# 9volt_rail.net
KiCad netlist of a schematic drawn in EAGLE
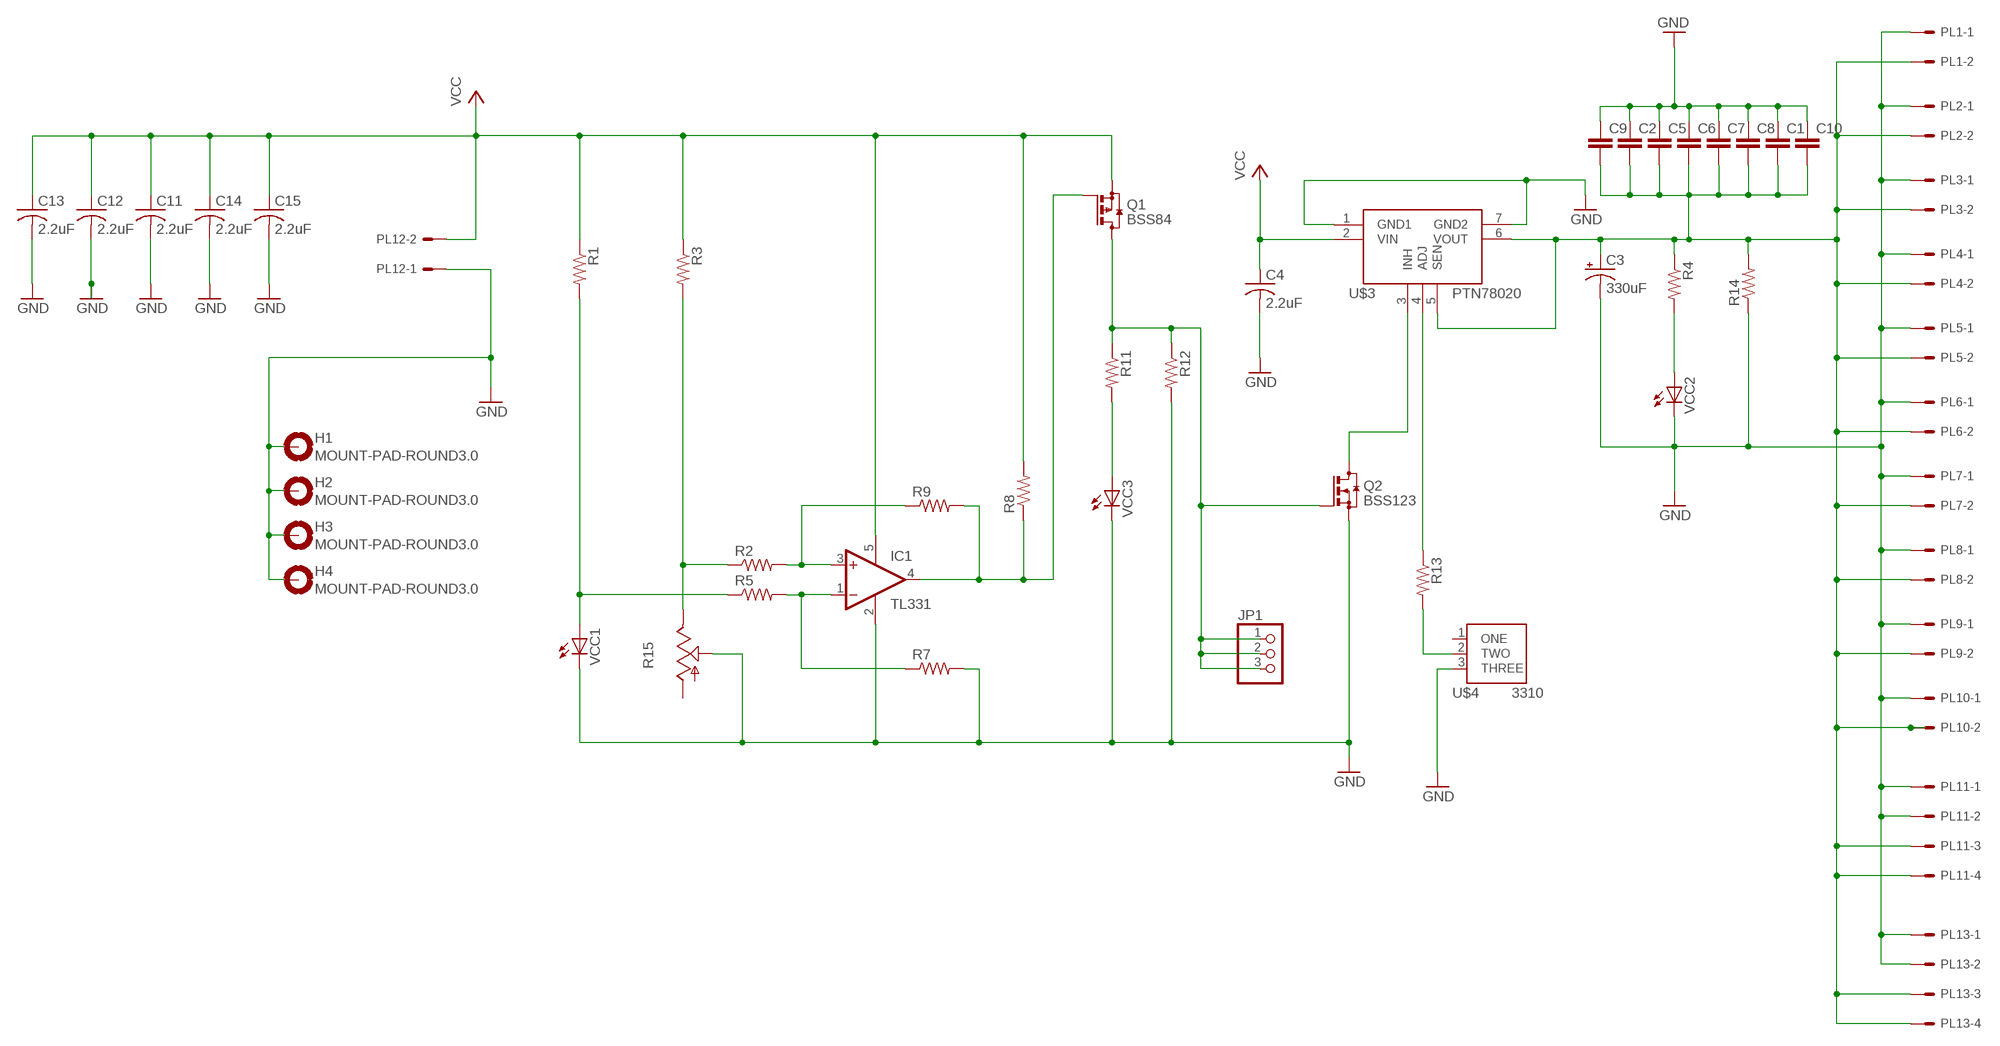
[diagram p0: schematic, sheet 1]

(export (version "E")
  (design (tool "Eeschema 10.0.6"))
  (components
    (comp (ref "C1")
      (value "C-EUC0805")
      (footprint "eagle-import:C0805")
      (libsource (lib "eagle-import") (part "C-EUC0805"))
    )
    (comp (ref "C2")
      (value "C-EUC0805")
      (footprint "eagle-import:C0805")
      (libsource (lib "eagle-import") (part "C-EUC0805"))
    )
    (comp (ref "C3")
      (value "330uF")
      (footprint "eagle-import:E5-10,5")
      (libsource (lib "eagle-import") (part "CPOL-USE5-10.5"))
    )
    (comp (ref "C4")
      (value "2.2uF")
      (footprint "eagle-import:C0805")
      (libsource (lib "eagle-import") (part "C-USC0805"))
    )
    (comp (ref "C5")
      (value "C-EUC0805")
      (footprint "eagle-import:C0805")
      (libsource (lib "eagle-import") (part "C-EUC0805"))
    )
    (comp (ref "C6")
      (value "C-EUC0805")
      (footprint "eagle-import:C0805")
      (libsource (lib "eagle-import") (part "C-EUC0805"))
    )
    (comp (ref "C7")
      (value "C-EUC0805")
      (footprint "eagle-import:C0805")
      (libsource (lib "eagle-import") (part "C-EUC0805"))
    )
    (comp (ref "C8")
      (value "C-EUC0805")
      (footprint "eagle-import:C0805")
      (libsource (lib "eagle-import") (part "C-EUC0805"))
    )
    (comp (ref "C9")
      (value "C-EUC0805")
      (footprint "eagle-import:C0805")
      (libsource (lib "eagle-import") (part "C-EUC0805"))
    )
    (comp (ref "C10")
      (value "C-EUC0805")
      (footprint "eagle-import:C0805")
      (libsource (lib "eagle-import") (part "C-EUC0805"))
    )
    (comp (ref "C11")
      (value "2.2uF")
      (footprint "eagle-import:C0805")
      (libsource (lib "eagle-import") (part "C-USC0805"))
    )
    (comp (ref "C12")
      (value "2.2uF")
      (footprint "eagle-import:C0805")
      (libsource (lib "eagle-import") (part "C-USC0805"))
    )
    (comp (ref "C13")
      (value "2.2uF")
      (footprint "eagle-import:C0805")
      (libsource (lib "eagle-import") (part "C-USC0805"))
    )
    (comp (ref "C14")
      (value "2.2uF")
      (footprint "eagle-import:C0805")
      (libsource (lib "eagle-import") (part "C-USC0805"))
    )
    (comp (ref "C15")
      (value "2.2uF")
      (footprint "eagle-import:C0805")
      (libsource (lib "eagle-import") (part "C-USC0805"))
    )
    (comp (ref "H1")
      (value "MOUNT-PAD-ROUND3.0")
      (footprint "eagle-import:3,0-PAD")
      (libsource (lib "eagle-import") (part "MOUNT-PAD-ROUND3.0"))
    )
    (comp (ref "H2")
      (value "MOUNT-PAD-ROUND3.0")
      (footprint "eagle-import:3,0-PAD")
      (libsource (lib "eagle-import") (part "MOUNT-PAD-ROUND3.0"))
    )
    (comp (ref "H3")
      (value "MOUNT-PAD-ROUND3.0")
      (footprint "eagle-import:3,0-PAD")
      (libsource (lib "eagle-import") (part "MOUNT-PAD-ROUND3.0"))
    )
    (comp (ref "H4")
      (value "MOUNT-PAD-ROUND3.0")
      (footprint "eagle-import:3,0-PAD")
      (libsource (lib "eagle-import") (part "MOUNT-PAD-ROUND3.0"))
    )
    (comp (ref "IC1")
      (value "TL331")
      (footprint "eagle-import:DBV-R-PDSO-G5")
      (libsource (lib "eagle-import") (part "TL331"))
    )
    (comp (ref "JP1")
      (value "PINHD-1X3")
      (footprint "eagle-import:1X03")
      (libsource (lib "eagle-import") (part "PINHD-1X3"))
    )
    (comp (ref "PL1")
      (value "555X-2H")
      (footprint "eagle-import:5569-2")
      (libsource (lib "eagle-import") (part "555X-2H"))
    )
    (comp (ref "PL2")
      (value "555X-2H")
      (footprint "eagle-import:5569-2")
      (libsource (lib "eagle-import") (part "555X-2H"))
    )
    (comp (ref "PL3")
      (value "555X-2H")
      (footprint "eagle-import:5569-2")
      (libsource (lib "eagle-import") (part "555X-2H"))
    )
    (comp (ref "PL4")
      (value "555X-2H")
      (footprint "eagle-import:5569-2")
      (libsource (lib "eagle-import") (part "555X-2H"))
    )
    (comp (ref "PL5")
      (value "555X-2H")
      (footprint "eagle-import:5569-2")
      (libsource (lib "eagle-import") (part "555X-2H"))
    )
    (comp (ref "PL6")
      (value "555X-2H")
      (footprint "eagle-import:5569-2")
      (libsource (lib "eagle-import") (part "555X-2H"))
    )
    (comp (ref "PL7")
      (value "555X-2H")
      (footprint "eagle-import:5569-2")
      (libsource (lib "eagle-import") (part "555X-2H"))
    )
    (comp (ref "PL8")
      (value "555X-2H")
      (footprint "eagle-import:5569-2")
      (libsource (lib "eagle-import") (part "555X-2H"))
    )
    (comp (ref "PL9")
      (value "555X-2H")
      (footprint "eagle-import:5569-2")
      (libsource (lib "eagle-import") (part "555X-2H"))
    )
    (comp (ref "PL10")
      (value "555X-2H")
      (footprint "eagle-import:5569-2")
      (libsource (lib "eagle-import") (part "555X-2H"))
    )
    (comp (ref "PL11")
      (value "555X-4H")
      (footprint "eagle-import:5569-4")
      (libsource (lib "eagle-import") (part "555X-4H"))
    )
    (comp (ref "PL12")
      (value "555X-2H")
      (footprint "eagle-import:5569-2")
      (libsource (lib "eagle-import") (part "555X-2H"))
    )
    (comp (ref "PL13")
      (value "555X-4H")
      (footprint "eagle-import:5569-4")
      (libsource (lib "eagle-import") (part "555X-4H"))
    )
    (comp (ref "Q1")
      (value "BSS84")
      (footprint "eagle-import:SOT23")
      (libsource (lib "eagle-import") (part "BSS84"))
    )
    (comp (ref "Q2")
      (value "BSS123")
      (footprint "eagle-import:SOT23")
      (libsource (lib "eagle-import") (part "BSS123"))
    )
    (comp (ref "R1")
      (value "R-US_M0805")
      (footprint "eagle-import:M0805")
      (libsource (lib "eagle-import") (part "R-US_M0805"))
    )
    (comp (ref "R2")
      (value "R-US_M0805")
      (footprint "eagle-import:M0805")
      (libsource (lib "eagle-import") (part "R-US_M0805"))
    )
    (comp (ref "R3")
      (value "R-US_M0805")
      (footprint "eagle-import:M0805")
      (libsource (lib "eagle-import") (part "R-US_M0805"))
    )
    (comp (ref "R4")
      (value "R-US_M0805")
      (footprint "eagle-import:M0805")
      (libsource (lib "eagle-import") (part "R-US_M0805"))
    )
    (comp (ref "R5")
      (value "R-US_M0805")
      (footprint "eagle-import:M0805")
      (libsource (lib "eagle-import") (part "R-US_M0805"))
    )
    (comp (ref "R7")
      (value "R-US_M0805")
      (footprint "eagle-import:M0805")
      (libsource (lib "eagle-import") (part "R-US_M0805"))
    )
    (comp (ref "R8")
      (value "R-US_M0805")
      (footprint "eagle-import:M0805")
      (libsource (lib "eagle-import") (part "R-US_M0805"))
    )
    (comp (ref "R9")
      (value "R-US_M0805")
      (footprint "eagle-import:M0805")
      (libsource (lib "eagle-import") (part "R-US_M0805"))
    )
    (comp (ref "R11")
      (value "R-US_M0805")
      (footprint "eagle-import:M0805")
      (libsource (lib "eagle-import") (part "R-US_M0805"))
    )
    (comp (ref "R12")
      (value "R-US_M0805")
      (footprint "eagle-import:M0805")
      (libsource (lib "eagle-import") (part "R-US_M0805"))
    )
    (comp (ref "R13")
      (value "R-US_M0805")
      (footprint "eagle-import:M0805")
      (libsource (lib "eagle-import") (part "R-US_M0805"))
    )
    (comp (ref "R14")
      (value "R-US_0617/17")
      (footprint "eagle-import:0617_17")
      (libsource (lib "eagle-import") (part "resistor_R-US_0617/17"))
    )
    (comp (ref "R15")
      (value "TRIM_US-S63P")
      (footprint "eagle-import:S63P")
      (libsource (lib "eagle-import") (part "TRIM_US-S63P"))
    )
    (comp (ref "U$3")
      (value "PTH78020-SMD")
      (footprint "eagle-import:PTN78020-SND")
      (libsource (lib "eagle-import") (part "PTH78020-SMD"))
    )
    (comp (ref "U$4")
      (value "3310-001")
      (footprint "eagle-import:3310-001-TH")
      (libsource (lib "eagle-import") (part "3310-001"))
    )
    (comp (ref "VCC1")
      (value "LED5MM")
      (footprint "eagle-import:LED5MM")
      (libsource (lib "eagle-import") (part "LED5MM"))
    )
    (comp (ref "VCC2")
      (value "LED5MM")
      (footprint "eagle-import:LED5MM")
      (libsource (lib "eagle-import") (part "LED5MM"))
    )
    (comp (ref "VCC3")
      (value "LED5MM")
      (footprint "eagle-import:LED5MM")
      (libsource (lib "eagle-import") (part "LED5MM"))
    )
  )
  (nets
    (net (code "1") (name "GND") (class "Default")
      (node (ref "C1") (pin "1") (pinfunction "1_1") (pintype "passive"))
      (node (ref "C10") (pin "1") (pinfunction "1_1") (pintype "passive"))
      (node (ref "C11") (pin "2") (pinfunction "2_2") (pintype "passive"))
      (node (ref "C12") (pin "2") (pinfunction "2_2") (pintype "passive"))
      (node (ref "C13") (pin "2") (pinfunction "2_2") (pintype "passive"))
      (node (ref "C14") (pin "2") (pinfunction "2_2") (pintype "passive"))
      (node (ref "C15") (pin "2") (pinfunction "2_2") (pintype "passive"))
      (node (ref "C2") (pin "1") (pinfunction "1_1") (pintype "passive"))
      (node (ref "C3") (pin "-") (pinfunction "-_-") (pintype "passive"))
      (node (ref "C4") (pin "2") (pinfunction "2_2") (pintype "passive"))
      (node (ref "C5") (pin "1") (pinfunction "1_1") (pintype "passive"))
      (node (ref "C6") (pin "1") (pinfunction "1_1") (pintype "passive"))
      (node (ref "C7") (pin "1") (pinfunction "1_1") (pintype "passive"))
      (node (ref "C8") (pin "1") (pinfunction "1_1") (pintype "passive"))
      (node (ref "C9") (pin "1") (pinfunction "1_1") (pintype "passive"))
      (node (ref "H1") (pin "B3,0") (pinfunction "MOUNT_B3,0") (pintype "passive"))
      (node (ref "H2") (pin "B3,0") (pinfunction "MOUNT_B3,0") (pintype "passive"))
      (node (ref "H3") (pin "B3,0") (pinfunction "MOUNT_B3,0") (pintype "passive"))
      (node (ref "H4") (pin "B3,0") (pinfunction "MOUNT_B3,0") (pintype "passive"))
      (node (ref "IC1") (pin "2") (pinfunction "GND_2") (pintype "power_in"))
      (node (ref "PL1") (pin "1") (pinfunction "S_1") (pintype "passive"))
      (node (ref "PL10") (pin "1") (pinfunction "S_1") (pintype "passive"))
      (node (ref "PL11") (pin "1") (pinfunction "S_1") (pintype "passive"))
      (node (ref "PL11") (pin "2") (pinfunction "S_2") (pintype "passive"))
      (node (ref "PL12") (pin "1") (pinfunction "S_1") (pintype "passive"))
      (node (ref "PL13") (pin "1") (pinfunction "S_1") (pintype "passive"))
      (node (ref "PL13") (pin "2") (pinfunction "S_2") (pintype "passive"))
      (node (ref "PL2") (pin "1") (pinfunction "S_1") (pintype "passive"))
      (node (ref "PL3") (pin "1") (pinfunction "S_1") (pintype "passive"))
      (node (ref "PL4") (pin "1") (pinfunction "S_1") (pintype "passive"))
      (node (ref "PL5") (pin "1") (pinfunction "S_1") (pintype "passive"))
      (node (ref "PL6") (pin "1") (pinfunction "S_1") (pintype "passive"))
      (node (ref "PL7") (pin "1") (pinfunction "S_1") (pintype "passive"))
      (node (ref "PL8") (pin "1") (pinfunction "S_1") (pintype "passive"))
      (node (ref "PL9") (pin "1") (pinfunction "S_1") (pintype "passive"))
      (node (ref "Q2") (pin "2") (pinfunction "S_2") (pintype "passive"))
      (node (ref "R12") (pin "2") (pinfunction "2_2") (pintype "passive"))
      (node (ref "R14") (pin "1") (pinfunction "1_1") (pintype "passive"))
      (node (ref "R15") (pin "S") (pinfunction "S_S") (pintype "passive"))
      (node (ref "R7") (pin "2") (pinfunction "2_2") (pintype "passive"))
      (node (ref "U$3") (pin "1") (pinfunction "GND1_1") (pintype "bidirectional"))
      (node (ref "U$3") (pin "7") (pinfunction "GND2_7") (pintype "bidirectional"))
      (node (ref "U$4") (pin "3") (pinfunction "THREE_3") (pintype "bidirectional"))
      (node (ref "VCC1") (pin "K") (pinfunction "C_K") (pintype "passive"))
      (node (ref "VCC2") (pin "K") (pinfunction "C_K") (pintype "passive"))
      (node (ref "VCC3") (pin "K") (pinfunction "C_K") (pintype "passive"))
    )
    (net (code "2") (name "Net-(IC1-+IN)") (class "Default")
      (node (ref "IC1") (pin "3") (pinfunction "+IN_3") (pintype "input"))
      (node (ref "R2") (pin "2") (pinfunction "2_2") (pintype "passive"))
      (node (ref "R9") (pin "1") (pinfunction "1_1") (pintype "passive"))
    )
    (net (code "3") (name "Net-(IC1--IN)") (class "Default")
      (node (ref "IC1") (pin "1") (pinfunction "-IN_1") (pintype "input"))
      (node (ref "R5") (pin "2") (pinfunction "2_2") (pintype "passive"))
      (node (ref "R7") (pin "1") (pinfunction "1_1") (pintype "passive"))
    )
    (net (code "4") (name "Net-(IC1-OUT)") (class "Default")
      (node (ref "IC1") (pin "4") (pinfunction "OUT_4") (pintype "output"))
      (node (ref "Q1") (pin "1") (pinfunction "G_1") (pintype "passive"))
      (node (ref "R8") (pin "1") (pinfunction "1_1") (pintype "passive"))
      (node (ref "R9") (pin "2") (pinfunction "2_2") (pintype "passive"))
    )
    (net (code "5") (name "Net-(PL10B-S)") (class "Default")
      (node (ref "C1") (pin "2") (pinfunction "2_2") (pintype "passive"))
      (node (ref "C10") (pin "2") (pinfunction "2_2") (pintype "passive"))
      (node (ref "C2") (pin "2") (pinfunction "2_2") (pintype "passive"))
      (node (ref "C3") (pin "+") (pinfunction "+_+") (pintype "passive"))
      (node (ref "C5") (pin "2") (pinfunction "2_2") (pintype "passive"))
      (node (ref "C6") (pin "2") (pinfunction "2_2") (pintype "passive"))
      (node (ref "C7") (pin "2") (pinfunction "2_2") (pintype "passive"))
      (node (ref "C8") (pin "2") (pinfunction "2_2") (pintype "passive"))
      (node (ref "C9") (pin "2") (pinfunction "2_2") (pintype "passive"))
      (node (ref "PL1") (pin "2") (pinfunction "S_2") (pintype "passive"))
      (node (ref "PL10") (pin "2") (pinfunction "S_2") (pintype "passive"))
      (node (ref "PL11") (pin "3") (pinfunction "S_3") (pintype "passive"))
      (node (ref "PL11") (pin "4") (pinfunction "S_4") (pintype "passive"))
      (node (ref "PL13") (pin "3") (pinfunction "S_3") (pintype "passive"))
      (node (ref "PL13") (pin "4") (pinfunction "S_4") (pintype "passive"))
      (node (ref "PL2") (pin "2") (pinfunction "S_2") (pintype "passive"))
      (node (ref "PL3") (pin "2") (pinfunction "S_2") (pintype "passive"))
      (node (ref "PL4") (pin "2") (pinfunction "S_2") (pintype "passive"))
      (node (ref "PL5") (pin "2") (pinfunction "S_2") (pintype "passive"))
      (node (ref "PL6") (pin "2") (pinfunction "S_2") (pintype "passive"))
      (node (ref "PL7") (pin "2") (pinfunction "S_2") (pintype "passive"))
      (node (ref "PL8") (pin "2") (pinfunction "S_2") (pintype "passive"))
      (node (ref "PL9") (pin "2") (pinfunction "S_2") (pintype "passive"))
      (node (ref "R14") (pin "2") (pinfunction "2_2") (pintype "passive"))
      (node (ref "R4") (pin "1") (pinfunction "1_1") (pintype "passive"))
      (node (ref "U$3") (pin "5") (pinfunction "SEN_5") (pintype "bidirectional"))
      (node (ref "U$3") (pin "6") (pinfunction "VOUT_6") (pintype "bidirectional"))
    )
    (net (code "6") (name "Net-(Q1-D)") (class "Default")
      (node (ref "JP1") (pin "1") (pinfunction "1_1") (pintype "passive"))
      (node (ref "JP1") (pin "2") (pinfunction "2_2") (pintype "passive"))
      (node (ref "JP1") (pin "3") (pinfunction "3_3") (pintype "passive"))
      (node (ref "Q1") (pin "3") (pinfunction "D_3") (pintype "passive"))
      (node (ref "Q2") (pin "1") (pinfunction "G_1") (pintype "passive"))
      (node (ref "R11") (pin "1") (pinfunction "1_1") (pintype "passive"))
      (node (ref "R12") (pin "1") (pinfunction "1_1") (pintype "passive"))
    )
    (net (code "7") (name "Net-(Q2-D)") (class "Default")
      (node (ref "Q2") (pin "3") (pinfunction "D_3") (pintype "passive"))
      (node (ref "U$3") (pin "3") (pinfunction "INH_3") (pintype "bidirectional"))
    )
    (net (code "8") (name "Net-(R1-Pad2)") (class "Default")
      (node (ref "R1") (pin "2") (pinfunction "2_2") (pintype "passive"))
      (node (ref "R5") (pin "1") (pinfunction "1_1") (pintype "passive"))
      (node (ref "VCC1") (pin "A") (pinfunction "A_A") (pintype "passive"))
    )
    (net (code "9") (name "Net-(R4-Pad2)") (class "Default")
      (node (ref "R4") (pin "2") (pinfunction "2_2") (pintype "passive"))
      (node (ref "VCC2") (pin "A") (pinfunction "A_A") (pintype "passive"))
    )
    (net (code "10") (name "Net-(R11-Pad2)") (class "Default")
      (node (ref "R11") (pin "2") (pinfunction "2_2") (pintype "passive"))
      (node (ref "VCC3") (pin "A") (pinfunction "A_A") (pintype "passive"))
    )
    (net (code "11") (name "Net-(R15-PadE)") (class "Default")
      (node (ref "R15") (pin "E") (pinfunction "E_E") (pintype "passive"))
      (node (ref "R2") (pin "1") (pinfunction "1_1") (pintype "passive"))
      (node (ref "R3") (pin "2") (pinfunction "2_2") (pintype "passive"))
    )
    (net (code "12") (name "Net-(U$3-ADJ)") (class "Default")
      (node (ref "R13") (pin "1") (pinfunction "1_1") (pintype "passive"))
      (node (ref "U$3") (pin "4") (pinfunction "ADJ_4") (pintype "bidirectional"))
    )
    (net (code "13") (name "Net-(U$4-TWO)") (class "Default")
      (node (ref "R13") (pin "2") (pinfunction "2_2") (pintype "passive"))
      (node (ref "U$4") (pin "2") (pinfunction "TWO_2") (pintype "bidirectional"))
    )
    (net (code "14") (name "VCC") (class "Default")
      (node (ref "C11") (pin "1") (pinfunction "1_1") (pintype "passive"))
      (node (ref "C12") (pin "1") (pinfunction "1_1") (pintype "passive"))
      (node (ref "C13") (pin "1") (pinfunction "1_1") (pintype "passive"))
      (node (ref "C14") (pin "1") (pinfunction "1_1") (pintype "passive"))
      (node (ref "C15") (pin "1") (pinfunction "1_1") (pintype "passive"))
      (node (ref "C4") (pin "1") (pinfunction "1_1") (pintype "passive"))
      (node (ref "IC1") (pin "5") (pinfunction "V+_5") (pintype "power_in"))
      (node (ref "PL12") (pin "2") (pinfunction "S_2") (pintype "passive"))
      (node (ref "Q1") (pin "2") (pinfunction "S_2") (pintype "passive"))
      (node (ref "R1") (pin "1") (pinfunction "1_1") (pintype "passive"))
      (node (ref "R3") (pin "1") (pinfunction "1_1") (pintype "passive"))
      (node (ref "R8") (pin "2") (pinfunction "2_2") (pintype "passive"))
      (node (ref "U$3") (pin "2") (pinfunction "VIN_2") (pintype "bidirectional"))
    )
    (net (code "15") (name "unconnected-(R15-PadA)") (class "Default")
      (node (ref "R15") (pin "A") (pinfunction "A_A") (pintype "passive"))
    )
    (net (code "16") (name "unconnected-(U$4-ONE-Pad1)") (class "Default")
      (node (ref "U$4") (pin "1") (pinfunction "ONE_1") (pintype "bidirectional"))
    )
  )
)
